# STM32-NRF24L01.net
KiCad netlist of a schematic drawn in EAGLE
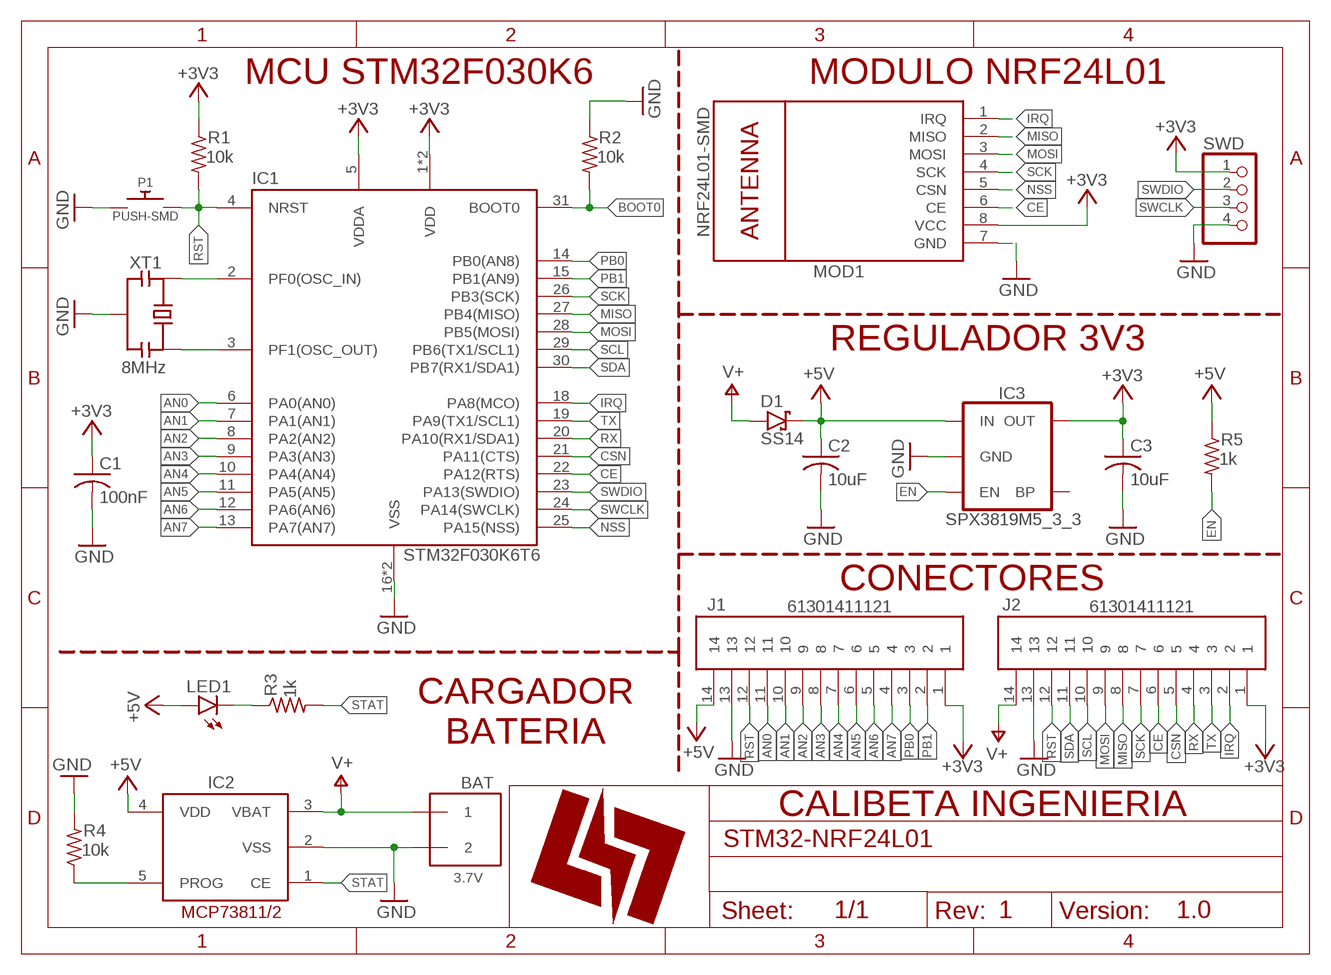
[diagram p0: schematic, sheet 1]

(export (version "E")
  (design (tool "Eeschema 10.0.6"))
  (components
    (comp (ref "BAT")
      (value "3.7V")
      (footprint "eagle-import:S2B-PH-SM4")
      (libsource (lib "eagle-import") (part "JST-2PIN-PH-SM4"))
    )
    (comp (ref "C1")
      (value "100nF")
      (footprint "eagle-import:C0805")
      (libsource (lib "eagle-import") (part "CAPC0805"))
    )
    (comp (ref "C2")
      (value "10uF")
      (footprint "eagle-import:C0805")
      (libsource (lib "eagle-import") (part "CAPC0805"))
    )
    (comp (ref "C3")
      (value "10uF")
      (footprint "eagle-import:C0805")
      (libsource (lib "eagle-import") (part "CAPC0805"))
    )
    (comp (ref "D1")
      (value "SS14")
      (footprint "eagle-import:DO-214AC")
      (libsource (lib "eagle-import") (part "SS14"))
    )
    (comp (ref "IC1")
      (value "STM32F030K6T6")
      (footprint "eagle-import:LQFP32")
      (libsource (lib "eagle-import") (part "STM32F030K6T6"))
    )
    (comp (ref "IC2")
      (value "MCP73811/2")
      (footprint "eagle-import:SOT23-5L")
      (libsource (lib "eagle-import") (part "MCP73811/2"))
    )
    (comp (ref "IC3")
      (value "SPX3819M5_3_3")
      (footprint "eagle-import:SOT23-5")
      (libsource (lib "eagle-import") (part "V_REG_SPX3819-SOT23-5"))
    )
    (comp (ref "J1")
      (value "61301411121")
      (footprint "eagle-import:61301411121")
      (fields
        (field (name "DIGIKEY_PART_NUMBER") "732-5325-ND")
        (field (name "MANUFACTURER") "Wurth Electronics Inc.")
        (field (name "CREATED_BY") "PCBLayout.com")
      )
      (libsource (lib "eagle-import") (part "61301411121"))
    )
    (comp (ref "J2")
      (value "61301411121")
      (footprint "eagle-import:61301411121")
      (fields
        (field (name "DIGIKEY_PART_NUMBER") "732-5325-ND")
        (field (name "MANUFACTURER") "Wurth Electronics Inc.")
        (field (name "CREATED_BY") "PCBLayout.com")
      )
      (libsource (lib "eagle-import") (part "61301411121"))
    )
    (comp (ref "LED1")
      (value "LED-ROJO0805")
      (footprint "eagle-import:LED0805-ROJO")
      (libsource (lib "eagle-import") (part "LED-ROJO0805"))
    )
    (comp (ref "MOD1")
      (value "NRF24L01-SMD")
      (footprint "eagle-import:NRF24L01-SMD")
      (libsource (lib "eagle-import") (part "NRF24L01-SMD"))
    )
    (comp (ref "P1")
      (value "PUSH-SMD")
      (footprint "eagle-import:ST-SMD-6X3.5MM")
      (libsource (lib "eagle-import") (part "PULSADOR-SMD-6035"))
    )
    (comp (ref "R1")
      (value "10k")
      (footprint "eagle-import:R0805")
      (libsource (lib "eagle-import") (part "RESISTOR_R0805"))
    )
    (comp (ref "R2")
      (value "10k")
      (footprint "eagle-import:R0805")
      (libsource (lib "eagle-import") (part "RESISTOR_R0805"))
    )
    (comp (ref "R3")
      (value "1k")
      (footprint "eagle-import:R0805")
      (libsource (lib "eagle-import") (part "RESISTOR_R0805"))
    )
    (comp (ref "R4")
      (value "10k")
      (footprint "eagle-import:R0805")
      (libsource (lib "eagle-import") (part "RESISTOR_R0805"))
    )
    (comp (ref "R5")
      (value "1k")
      (footprint "eagle-import:R0805")
      (libsource (lib "eagle-import") (part "RESISTOR_R0805"))
    )
    (comp (ref "SWD")
      (value "PINHD-1X4/90")
      (footprint "eagle-import:1X04_90")
      (libsource (lib "eagle-import") (part "PINHD-1X4/90"))
    )
    (comp (ref "U$1")
      (value "A5_H-LOGO")
      (footprint "eagle-import:LOGO-10MM")
      (libsource (lib "eagle-import") (part "A5_H-LOGO"))
    )
    (comp (ref "XT1")
      (value "8MHz")
      (footprint "eagle-import:3-SMD")
      (libsource (lib "eagle-import") (part "CSTNE8M00G55-R0"))
    )
  )
  (nets
    (net (code "1") (name "+3V3") (class "Default")
      (node (ref "C1") (pin "1") (pinfunction "1_1") (pintype "passive"))
      (node (ref "C3") (pin "1") (pinfunction "1_1") (pintype "passive"))
      (node (ref "IC1") (pin "1") (pinfunction "VDD_1") (pintype "power_in"))
      (node (ref "IC1") (pin "17") (pinfunction "VDD_17") (pintype "power_in"))
      (node (ref "IC1") (pin "5") (pinfunction "VDDA_5") (pintype "bidirectional"))
      (node (ref "IC3") (pin "5") (pinfunction "OUT_5") (pintype "passive"))
      (node (ref "J1") (pin "1") (pinfunction "1_1") (pintype "passive"))
      (node (ref "J2") (pin "1") (pinfunction "1_1") (pintype "passive"))
      (node (ref "MOD1") (pin "8") (pinfunction "VCC_8") (pintype "power_in"))
      (node (ref "R1") (pin "1") (pinfunction "1_1") (pintype "passive"))
      (node (ref "SWD") (pin "1") (pinfunction "1_1") (pintype "passive"))
    )
    (net (code "2") (name "+5V") (class "Default")
      (node (ref "C2") (pin "1") (pinfunction "1_1") (pintype "passive"))
      (node (ref "D1") (pin "K") (pinfunction "K_K") (pintype "passive"))
      (node (ref "IC2") (pin "4") (pinfunction "VDD_4") (pintype "power_in"))
      (node (ref "IC3") (pin "1") (pinfunction "IN_1") (pintype "input"))
      (node (ref "J1") (pin "14") (pinfunction "14_14") (pintype "passive"))
      (node (ref "LED1") (pin "A") (pinfunction "A_A") (pintype "passive"))
      (node (ref "R5") (pin "1") (pinfunction "1_1") (pintype "passive"))
    )
    (net (code "3") (name "AN0") (class "Default")
      (node (ref "IC1") (pin "6") (pinfunction "PA0(AN0)_6") (pintype "bidirectional"))
      (node (ref "J1") (pin "11") (pinfunction "11_11") (pintype "passive"))
    )
    (net (code "4") (name "AN1") (class "Default")
      (node (ref "IC1") (pin "7") (pinfunction "PA1(AN1)_7") (pintype "bidirectional"))
      (node (ref "J1") (pin "10") (pinfunction "10_10") (pintype "passive"))
    )
    (net (code "5") (name "AN2") (class "Default")
      (node (ref "IC1") (pin "8") (pinfunction "PA2(AN2)_8") (pintype "bidirectional"))
      (node (ref "J1") (pin "9") (pinfunction "9_9") (pintype "passive"))
    )
    (net (code "6") (name "AN3") (class "Default")
      (node (ref "IC1") (pin "9") (pinfunction "PA3(AN3)_9") (pintype "bidirectional"))
      (node (ref "J1") (pin "8") (pinfunction "8_8") (pintype "passive"))
    )
    (net (code "7") (name "AN4") (class "Default")
      (node (ref "IC1") (pin "10") (pinfunction "PA4(AN4)_10") (pintype "bidirectional"))
      (node (ref "J1") (pin "7") (pinfunction "7_7") (pintype "passive"))
    )
    (net (code "8") (name "AN5") (class "Default")
      (node (ref "IC1") (pin "11") (pinfunction "PA5(AN5)_11") (pintype "bidirectional"))
      (node (ref "J1") (pin "6") (pinfunction "6_6") (pintype "passive"))
    )
    (net (code "9") (name "AN6") (class "Default")
      (node (ref "IC1") (pin "12") (pinfunction "PA6(AN6)_12") (pintype "bidirectional"))
      (node (ref "J1") (pin "5") (pinfunction "5_5") (pintype "passive"))
    )
    (net (code "10") (name "AN7") (class "Default")
      (node (ref "IC1") (pin "13") (pinfunction "PA7(AN7)_13") (pintype "bidirectional"))
      (node (ref "J1") (pin "4") (pinfunction "4_4") (pintype "passive"))
    )
    (net (code "11") (name "BOOT0") (class "Default")
      (node (ref "IC1") (pin "31") (pinfunction "BOOT0_31") (pintype "bidirectional"))
      (node (ref "R2") (pin "2") (pinfunction "2_2") (pintype "passive"))
    )
    (net (code "12") (name "CE") (class "Default")
      (node (ref "IC1") (pin "22") (pinfunction "PA12(RTS)_22") (pintype "bidirectional"))
      (node (ref "J2") (pin "6") (pinfunction "6_6") (pintype "passive"))
      (node (ref "MOD1") (pin "6") (pinfunction "CE_6") (pintype "bidirectional"))
    )
    (net (code "13") (name "CSN") (class "Default")
      (node (ref "IC1") (pin "21") (pinfunction "PA11(CTS)_21") (pintype "bidirectional"))
      (node (ref "J2") (pin "5") (pinfunction "5_5") (pintype "passive"))
    )
    (net (code "14") (name "EN") (class "Default")
      (node (ref "IC3") (pin "3") (pinfunction "EN_3") (pintype "input"))
      (node (ref "R5") (pin "2") (pinfunction "2_2") (pintype "passive"))
    )
    (net (code "15") (name "GND") (class "Default")
      (node (ref "BAT") (pin "2") (pinfunction "2_2") (pintype "passive"))
      (node (ref "C1") (pin "2") (pinfunction "2_2") (pintype "passive"))
      (node (ref "C2") (pin "2") (pinfunction "2_2") (pintype "passive"))
      (node (ref "C3") (pin "2") (pinfunction "2_2") (pintype "passive"))
      (node (ref "IC1") (pin "16") (pinfunction "VSS_16") (pintype "power_in"))
      (node (ref "IC1") (pin "32") (pinfunction "VSS_32") (pintype "power_in"))
      (node (ref "IC2") (pin "2") (pinfunction "VSS_2") (pintype "power_in"))
      (node (ref "IC3") (pin "2") (pinfunction "GND_2") (pintype "input"))
      (node (ref "J1") (pin "13") (pinfunction "13_13") (pintype "passive"))
      (node (ref "J2") (pin "13") (pinfunction "13_13") (pintype "passive"))
      (node (ref "MOD1") (pin "7") (pinfunction "GND_7") (pintype "power_in"))
      (node (ref "P1") (pin "1") (pinfunction "1_1") (pintype "passive"))
      (node (ref "R2") (pin "1") (pinfunction "1_1") (pintype "passive"))
      (node (ref "R4") (pin "2") (pinfunction "2_2") (pintype "passive"))
      (node (ref "SWD") (pin "4") (pinfunction "4_4") (pintype "passive"))
      (node (ref "XT1") (pin "2") (pinfunction "GND_2") (pintype "power_in"))
    )
    (net (code "16") (name "IRQ") (class "Default")
      (node (ref "IC1") (pin "18") (pinfunction "PA8(MCO)_18") (pintype "bidirectional"))
      (node (ref "J2") (pin "2") (pinfunction "2_2") (pintype "passive"))
      (node (ref "MOD1") (pin "1") (pinfunction "IRQ_1") (pintype "bidirectional"))
    )
    (net (code "17") (name "MISO") (class "Default")
      (node (ref "IC1") (pin "27") (pinfunction "PB4(MISO)_27") (pintype "bidirectional"))
      (node (ref "J2") (pin "8") (pinfunction "8_8") (pintype "passive"))
      (node (ref "MOD1") (pin "2") (pinfunction "MISO_2") (pintype "bidirectional"))
    )
    (net (code "18") (name "MOSI") (class "Default")
      (node (ref "IC1") (pin "28") (pinfunction "PB5(MOSI)_28") (pintype "bidirectional"))
      (node (ref "J2") (pin "9") (pinfunction "9_9") (pintype "passive"))
      (node (ref "MOD1") (pin "3") (pinfunction "MOSI_3") (pintype "bidirectional"))
    )
    (net (code "19") (name "NSS") (class "Default")
      (node (ref "IC1") (pin "25") (pinfunction "PA15(NSS)_25") (pintype "bidirectional"))
      (node (ref "MOD1") (pin "5") (pinfunction "CSN_5") (pintype "bidirectional"))
    )
    (net (code "20") (name "Net-(IC1-PF0(OSC_IN))") (class "Default")
      (node (ref "IC1") (pin "2") (pinfunction "PF0(OSC_IN)_2") (pintype "bidirectional"))
      (node (ref "XT1") (pin "1") (pinfunction "X1_1") (pintype "bidirectional"))
    )
    (net (code "21") (name "Net-(IC1-PF1(OSC_OUT))") (class "Default")
      (node (ref "IC1") (pin "3") (pinfunction "PF1(OSC_OUT)_3") (pintype "bidirectional"))
      (node (ref "XT1") (pin "3") (pinfunction "X2_3") (pintype "bidirectional"))
    )
    (net (code "22") (name "Net-(IC2-PROG)") (class "Default")
      (node (ref "IC2") (pin "5") (pinfunction "PROG_5") (pintype "input"))
      (node (ref "R4") (pin "1") (pinfunction "1_1") (pintype "passive"))
    )
    (net (code "23") (name "Net-(LED1-PadC)") (class "Default")
      (node (ref "LED1") (pin "C") (pinfunction "C_C") (pintype "passive"))
      (node (ref "R3") (pin "1") (pinfunction "1_1") (pintype "passive"))
    )
    (net (code "24") (name "PB0") (class "Default")
      (node (ref "IC1") (pin "14") (pinfunction "PB0(AN8)_14") (pintype "bidirectional"))
      (node (ref "J1") (pin "3") (pinfunction "3_3") (pintype "passive"))
    )
    (net (code "25") (name "PB1") (class "Default")
      (node (ref "IC1") (pin "15") (pinfunction "PB1(AN9)_15") (pintype "bidirectional"))
      (node (ref "J1") (pin "2") (pinfunction "2_2") (pintype "passive"))
    )
    (net (code "26") (name "RST") (class "Default")
      (node (ref "IC1") (pin "4") (pinfunction "NRST_4") (pintype "bidirectional"))
      (node (ref "J1") (pin "12") (pinfunction "12_12") (pintype "passive"))
      (node (ref "J2") (pin "12") (pinfunction "12_12") (pintype "passive"))
      (node (ref "P1") (pin "2") (pinfunction "2_2") (pintype "passive"))
      (node (ref "R1") (pin "2") (pinfunction "2_2") (pintype "passive"))
    )
    (net (code "27") (name "RX") (class "Default")
      (node (ref "IC1") (pin "20") (pinfunction "PA10(RX1/SDA1)_20") (pintype "bidirectional"))
      (node (ref "J2") (pin "4") (pinfunction "4_4") (pintype "passive"))
    )
    (net (code "28") (name "SCK") (class "Default")
      (node (ref "IC1") (pin "26") (pinfunction "PB3(SCK)_26") (pintype "bidirectional"))
      (node (ref "J2") (pin "7") (pinfunction "7_7") (pintype "passive"))
      (node (ref "MOD1") (pin "4") (pinfunction "SCK_4") (pintype "bidirectional"))
    )
    (net (code "29") (name "SCL") (class "Default")
      (node (ref "IC1") (pin "29") (pinfunction "PB6(TX1/SCL1)_29") (pintype "bidirectional"))
      (node (ref "J2") (pin "10") (pinfunction "10_10") (pintype "passive"))
    )
    (net (code "30") (name "SDA") (class "Default")
      (node (ref "IC1") (pin "30") (pinfunction "PB7(RX1/SDA1)_30") (pintype "bidirectional"))
      (node (ref "J2") (pin "11") (pinfunction "11_11") (pintype "passive"))
    )
    (net (code "31") (name "STAT") (class "Default")
      (node (ref "IC2") (pin "1") (pinfunction "CE_1") (pintype "input"))
      (node (ref "R3") (pin "2") (pinfunction "2_2") (pintype "passive"))
    )
    (net (code "32") (name "SWCLK") (class "Default")
      (node (ref "IC1") (pin "24") (pinfunction "PA14(SWCLK)_24") (pintype "bidirectional"))
      (node (ref "SWD") (pin "3") (pinfunction "3_3") (pintype "passive"))
    )
    (net (code "33") (name "SWDIO") (class "Default")
      (node (ref "IC1") (pin "23") (pinfunction "PA13(SWDIO)_23") (pintype "bidirectional"))
      (node (ref "SWD") (pin "2") (pinfunction "2_2") (pintype "passive"))
    )
    (net (code "34") (name "TX") (class "Default")
      (node (ref "IC1") (pin "19") (pinfunction "PA9(TX1/SCL1)_19") (pintype "bidirectional"))
      (node (ref "J2") (pin "3") (pinfunction "3_3") (pintype "passive"))
    )
    (net (code "35") (name "V+") (class "Default")
      (node (ref "BAT") (pin "1") (pinfunction "1_1") (pintype "passive"))
      (node (ref "D1") (pin "A") (pinfunction "A_A") (pintype "passive"))
      (node (ref "IC2") (pin "3") (pinfunction "VBAT_3") (pintype "bidirectional"))
      (node (ref "J2") (pin "14") (pinfunction "14_14") (pintype "passive"))
    )
    (net (code "36") (name "unconnected-(IC3-BP-Pad4)") (class "Default")
      (node (ref "IC3") (pin "4") (pinfunction "BP_4") (pintype "input"))
    )
  )
)
